# PageTurner.net
KiCad netlist of a schematic drawn in EAGLE
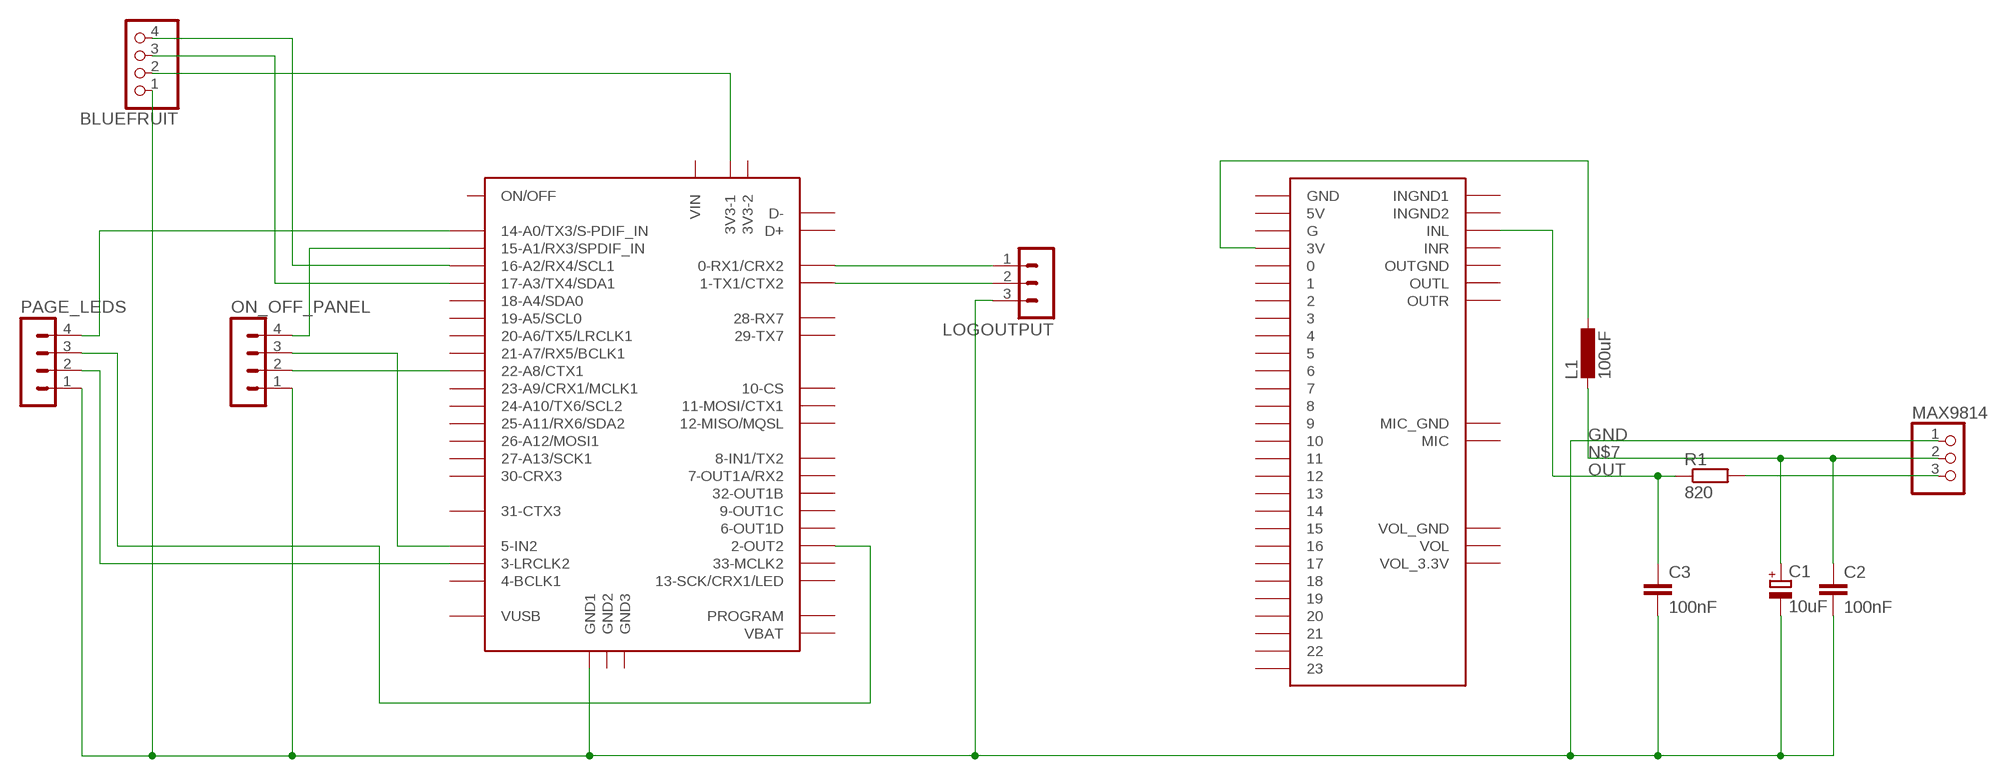
[diagram p0: schematic, sheet 1]

(export (version "E")
  (design (tool "Eeschema 10.0.6"))
  (components
    (comp (ref "BLUEFRUIT")
      (value "PINHD-1X4")
      (footprint "eagle-import:1X04")
      (libsource (lib "eagle-import") (part "PINHD-1X4"))
    )
    (comp (ref "C1")
      (value "10uF")
      (footprint "eagle-import:E2-4")
      (libsource (lib "eagle-import") (part "CPOL-EUE2-4"))
    )
    (comp (ref "C2")
      (value "100nF")
      (footprint "eagle-import:C025-040X050")
      (libsource (lib "eagle-import") (part "C-EU025-040X050"))
    )
    (comp (ref "C3")
      (value "100nF")
      (footprint "eagle-import:C025-040X050")
      (libsource (lib "eagle-import") (part "C-EU025-040X050"))
    )
    (comp (ref "L1")
      (value "100uF")
      (footprint "eagle-import:0207_5V")
      (libsource (lib "eagle-import") (part "L-EU0207/5V"))
    )
    (comp (ref "LOGOUTPUT")
      (value "MA03-1")
      (footprint "eagle-import:MA03-1")
      (libsource (lib "eagle-import") (part "MA03-1"))
    )
    (comp (ref "MAX9814")
      (value "PINHD-1X3")
      (footprint "eagle-import:1X03")
      (libsource (lib "eagle-import") (part "PINHD-1X3"))
    )
    (comp (ref "ON_OFF_PANEL")
      (value "MA04-1")
      (footprint "eagle-import:MA04-1")
      (libsource (lib "eagle-import") (part "MA04-1"))
    )
    (comp (ref "PAGE_LEDS")
      (value "MA04-1")
      (footprint "eagle-import:MA04-1")
      (libsource (lib "eagle-import") (part "MA04-1"))
    )
    (comp (ref "R1")
      (value "820")
      (footprint "eagle-import:0207_7")
      (libsource (lib "eagle-import") (part "R-EU_0207/7"))
    )
    (comp (ref "U$1")
      (value "TEENSY40")
      (footprint "eagle-import:TEENSY40")
      (libsource (lib "eagle-import") (part "TEENSY40"))
    )
    (comp (ref "U$2")
      (value "AUDIOSHIELD")
      (footprint "eagle-import:AUDIOSHIELD")
      (libsource (lib "eagle-import") (part "AUDIOSHIELD"))
    )
  )
  (nets
    (net (code "1") (name "/GND") (class "Default")
      (node (ref "BLUEFRUIT") (pin "1") (pinfunction "1_1") (pintype "passive"))
      (node (ref "C1") (pin "-") (pinfunction "-_-") (pintype "passive"))
      (node (ref "C2") (pin "2") (pinfunction "2_2") (pintype "passive"))
      (node (ref "C3") (pin "2") (pinfunction "2_2") (pintype "passive"))
      (node (ref "LOGOUTPUT") (pin "3") (pinfunction "3_3") (pintype "passive"))
      (node (ref "MAX9814") (pin "1") (pinfunction "1_1") (pintype "passive"))
      (node (ref "ON_OFF_PANEL") (pin "1") (pinfunction "1_1") (pintype "passive"))
      (node (ref "PAGE_LEDS") (pin "1") (pinfunction "1_1") (pintype "passive"))
      (node (ref "U$1") (pin "GND1") (pinfunction "GND1_GND1") (pintype "bidirectional"))
    )
    (net (code "2") (name "/N$7") (class "Default")
      (node (ref "C1") (pin "+") (pinfunction "+_+") (pintype "passive"))
      (node (ref "C2") (pin "1") (pinfunction "1_1") (pintype "passive"))
      (node (ref "L1") (pin "2") (pinfunction "2_2") (pintype "passive"))
      (node (ref "MAX9814") (pin "2") (pinfunction "2_2") (pintype "passive"))
    )
    (net (code "3") (name "/OUT") (class "Default")
      (node (ref "C3") (pin "1") (pinfunction "1_1") (pintype "passive"))
      (node (ref "R1") (pin "1") (pinfunction "1_1") (pintype "passive"))
      (node (ref "U$2") (pin "INL") (pinfunction "INL_INL") (pintype "input"))
    )
    (net (code "4") (name "Net-(BLUEFRUIT-Pad2)") (class "Default")
      (node (ref "BLUEFRUIT") (pin "2") (pinfunction "2_2") (pintype "passive"))
      (node (ref "U$1") (pin "3V3-1") (pinfunction "3V3-1_3V3-1") (pintype "bidirectional"))
    )
    (net (code "5") (name "Net-(BLUEFRUIT-Pad3)") (class "Default")
      (node (ref "BLUEFRUIT") (pin "3") (pinfunction "3_3") (pintype "passive"))
      (node (ref "U$1") (pin "17-A3/TX4/SDA1") (pinfunction "17-A3/TX4/SDA1_17-A3/TX4/SDA1") (pintype "bidirectional"))
    )
    (net (code "6") (name "Net-(BLUEFRUIT-Pad4)") (class "Default")
      (node (ref "BLUEFRUIT") (pin "4") (pinfunction "4_4") (pintype "passive"))
      (node (ref "U$1") (pin "16-A2/RX4/SCL1") (pinfunction "16-A2/RX4/SCL1_16-A2/RX4/SCL1") (pintype "bidirectional"))
    )
    (net (code "7") (name "Net-(L1-Pad1)") (class "Default")
      (node (ref "L1") (pin "1") (pinfunction "1_1") (pintype "passive"))
      (node (ref "U$2") (pin "3V") (pinfunction "3V_3V") (pintype "bidirectional"))
    )
    (net (code "8") (name "Net-(MAX9814-Pad3)") (class "Default")
      (node (ref "MAX9814") (pin "3") (pinfunction "3_3") (pintype "passive"))
      (node (ref "R1") (pin "2") (pinfunction "2_2") (pintype "passive"))
    )
    (net (code "9") (name "Net-(ON_OFF_PANEL-Pad2)") (class "Default")
      (node (ref "ON_OFF_PANEL") (pin "2") (pinfunction "2_2") (pintype "passive"))
      (node (ref "U$1") (pin "22-A8/CTX1") (pinfunction "22-A8/CTX1_22-A8/CTX1") (pintype "bidirectional"))
    )
    (net (code "10") (name "Net-(ON_OFF_PANEL-Pad3)") (class "Default")
      (node (ref "ON_OFF_PANEL") (pin "3") (pinfunction "3_3") (pintype "passive"))
      (node (ref "U$1") (pin "5-IN2") (pinfunction "5-IN2_5-IN2") (pintype "bidirectional"))
    )
    (net (code "11") (name "Net-(PAGE_LEDS-Pad2)") (class "Default")
      (node (ref "PAGE_LEDS") (pin "2") (pinfunction "2_2") (pintype "passive"))
      (node (ref "U$1") (pin "3-LRCLK2") (pinfunction "3-LRCLK2_3-LRCLK2") (pintype "bidirectional"))
    )
    (net (code "12") (name "Net-(PAGE_LEDS-Pad3)") (class "Default")
      (node (ref "PAGE_LEDS") (pin "3") (pinfunction "3_3") (pintype "passive"))
      (node (ref "U$1") (pin "2-OUT2") (pinfunction "2-OUT2_2-OUT2") (pintype "bidirectional"))
    )
    (net (code "13") (name "Net-(U$1-0-RX1{slash}CRX2)") (class "Default")
      (node (ref "LOGOUTPUT") (pin "1") (pinfunction "1_1") (pintype "passive"))
      (node (ref "U$1") (pin "0-RX1") (pinfunction "0-RX1/CRX2_0-RX1") (pintype "bidirectional"))
    )
    (net (code "14") (name "Net-(U$1-1-TX1{slash}CTX2)") (class "Default")
      (node (ref "LOGOUTPUT") (pin "2") (pinfunction "2_2") (pintype "passive"))
      (node (ref "U$1") (pin "1-TX1") (pinfunction "1-TX1/CTX2_1-TX1") (pintype "bidirectional"))
    )
    (net (code "15") (name "Net-(U$1-14-A0{slash}TX3{slash}S-PDIF_IN)") (class "Default")
      (node (ref "PAGE_LEDS") (pin "4") (pinfunction "4_4") (pintype "passive"))
      (node (ref "U$1") (pin "14-A0/TX3/S-PFI_OUT") (pinfunction "14-A0/TX3/S-PDIF_IN_14-A0/TX3/S-PFI_OUT") (pintype "bidirectional"))
    )
    (net (code "16") (name "Net-(U$1-15-A1{slash}RX3{slash}SPDIF_IN)") (class "Default")
      (node (ref "ON_OFF_PANEL") (pin "4") (pinfunction "4_4") (pintype "passive"))
      (node (ref "U$1") (pin "15-A1/RX3/S-PDIF_IN") (pinfunction "15-A1/RX3/SPDIF_IN_15-A1/RX3/S-PDIF_IN") (pintype "bidirectional"))
    )
    (net (code "17") (name "unconnected-(U$1-4-BCLK1-Pad4-BCLK2)") (class "Default")
      (node (ref "U$1") (pin "4-BCLK2") (pinfunction "4-BCLK1_4-BCLK2") (pintype "bidirectional"))
    )
    (net (code "18") (name "unconnected-(U$1-7-OUT1A{slash}RX2-Pad7-RX2{slash}OUT1A)") (class "Default")
      (node (ref "U$1") (pin "7-RX2/OUT1A") (pinfunction "7-OUT1A/RX2_7-RX2/OUT1A") (pintype "bidirectional"))
    )
    (net (code "19") (name "unconnected-(U$1-8-IN1{slash}TX2-Pad8-TX2{slash}IN1)") (class "Default")
      (node (ref "U$1") (pin "8-TX2/IN1") (pinfunction "8-IN1/TX2_8-TX2/IN1") (pintype "bidirectional"))
    )
    (net (code "20") (name "unconnected-(U$1-10-CS-Pad10-CS{slash}MQSR)") (class "Default")
      (node (ref "U$1") (pin "10-CS/MQSR") (pinfunction "10-CS_10-CS/MQSR") (pintype "bidirectional"))
    )
    (net (code "21") (name "unconnected-(U$1-12-MISO{slash}MQSL-Pad12-MIO{slash}MQSL)") (class "Default")
      (node (ref "U$1") (pin "12-MIO/MQSL") (pinfunction "12-MISO/MQSL_12-MIO/MQSL") (pintype "bidirectional"))
    )
    (net (code "22") (name "unconnected-(U$1-23-A9{slash}CRX1{slash}MCLK1-Pad23-A9{slash}CRX1{slash}CCLK1)") (class "Default")
      (node (ref "U$1") (pin "23-A9/CRX1/CCLK1") (pinfunction "23-A9/CRX1/MCLK1_23-A9/CRX1/CCLK1") (pintype "bidirectional"))
    )
    (net (code "23") (name "unconnected-(U$1-25-A11{slash}RX6{slash}SDA2-Pad25-A11{slash}SDA2)") (class "Default")
      (node (ref "U$1") (pin "25-A11/SDA2") (pinfunction "25-A11/RX6/SDA2_25-A11/SDA2") (pintype "bidirectional"))
    )
    (net (code "24") (name "unconnected-(U$1-32-OUT1B-Pad32-OUTB1)") (class "Default")
      (node (ref "U$1") (pin "32-OUTB1") (pinfunction "32-OUT1B_32-OUTB1") (pintype "bidirectional"))
    )
    (net (code "25") (name "unconnected-(U$1-Pad3V3-2)") (class "Default")
      (node (ref "U$1") (pin "3V3-2") (pinfunction "3V3-2_3V3-2") (pintype "bidirectional"))
    )
    (net (code "26") (name "unconnected-(U$1-Pad6-OUT1D)") (class "Default")
      (node (ref "U$1") (pin "6-OUT1D") (pinfunction "6-OUT1D_6-OUT1D") (pintype "bidirectional"))
    )
    (net (code "27") (name "unconnected-(U$1-Pad9-OUT1C)") (class "Default")
      (node (ref "U$1") (pin "9-OUT1C") (pinfunction "9-OUT1C_9-OUT1C") (pintype "bidirectional"))
    )
    (net (code "28") (name "unconnected-(U$1-Pad11-MOSI{slash}CTX1)") (class "Default")
      (node (ref "U$1") (pin "11-MOSI/CTX1") (pinfunction "11-MOSI/CTX1_11-MOSI/CTX1") (pintype "bidirectional"))
    )
    (net (code "29") (name "unconnected-(U$1-Pad13-SCK{slash}CRX1{slash}LED)") (class "Default")
      (node (ref "U$1") (pin "13-SCK/CRX1/LED") (pinfunction "13-SCK/CRX1/LED_13-SCK/CRX1/LED") (pintype "bidirectional"))
    )
    (net (code "30") (name "unconnected-(U$1-Pad18-A4{slash}SDA0)") (class "Default")
      (node (ref "U$1") (pin "18-A4/SDA0") (pinfunction "18-A4/SDA0_18-A4/SDA0") (pintype "bidirectional"))
    )
    (net (code "31") (name "unconnected-(U$1-Pad19-A5{slash}SCL0)") (class "Default")
      (node (ref "U$1") (pin "19-A5/SCL0") (pinfunction "19-A5/SCL0_19-A5/SCL0") (pintype "bidirectional"))
    )
    (net (code "32") (name "unconnected-(U$1-Pad20-A6{slash}TX5{slash}LRCLK1)") (class "Default")
      (node (ref "U$1") (pin "20-A6/TX5/LRCLK1") (pinfunction "20-A6/TX5/LRCLK1_20-A6/TX5/LRCLK1") (pintype "bidirectional"))
    )
    (net (code "33") (name "unconnected-(U$1-Pad21-A7{slash}RX5{slash}BCLK1)") (class "Default")
      (node (ref "U$1") (pin "21-A7/RX5/BCLK1") (pinfunction "21-A7/RX5/BCLK1_21-A7/RX5/BCLK1") (pintype "bidirectional"))
    )
    (net (code "34") (name "unconnected-(U$1-Pad24-A10{slash}TX6{slash}SCL2)") (class "Default")
      (node (ref "U$1") (pin "24-A10/TX6/SCL2") (pinfunction "24-A10/TX6/SCL2_24-A10/TX6/SCL2") (pintype "bidirectional"))
    )
    (net (code "35") (name "unconnected-(U$1-Pad26-A12{slash}MOSI1)") (class "Default")
      (node (ref "U$1") (pin "26-A12/MOSI1") (pinfunction "26-A12/MOSI1_26-A12/MOSI1") (pintype "bidirectional"))
    )
    (net (code "36") (name "unconnected-(U$1-Pad27-A13{slash}SCK1)") (class "Default")
      (node (ref "U$1") (pin "27-A13/SCK1") (pinfunction "27-A13/SCK1_27-A13/SCK1") (pintype "bidirectional"))
    )
    (net (code "37") (name "unconnected-(U$1-Pad28-RX7)") (class "Default")
      (node (ref "U$1") (pin "28-RX7") (pinfunction "28-RX7_28-RX7") (pintype "bidirectional"))
    )
    (net (code "38") (name "unconnected-(U$1-Pad29-TX7)") (class "Default")
      (node (ref "U$1") (pin "29-TX7") (pinfunction "29-TX7_29-TX7") (pintype "bidirectional"))
    )
    (net (code "39") (name "unconnected-(U$1-Pad30-CRX3)") (class "Default")
      (node (ref "U$1") (pin "30-CRX3") (pinfunction "30-CRX3_30-CRX3") (pintype "bidirectional"))
    )
    (net (code "40") (name "unconnected-(U$1-Pad31-CTX3)") (class "Default")
      (node (ref "U$1") (pin "31-CTX3") (pinfunction "31-CTX3_31-CTX3") (pintype "bidirectional"))
    )
    (net (code "41") (name "unconnected-(U$1-Pad33-MCLK2)") (class "Default")
      (node (ref "U$1") (pin "33-MCLK2") (pinfunction "33-MCLK2_33-MCLK2") (pintype "bidirectional"))
    )
    (net (code "42") (name "unconnected-(U$1-PadD+)") (class "Default")
      (node (ref "U$1") (pin "D+") (pinfunction "D+_D+") (pintype "bidirectional"))
    )
    (net (code "43") (name "unconnected-(U$1-PadD-)") (class "Default")
      (node (ref "U$1") (pin "D-") (pinfunction "D-_D-") (pintype "bidirectional"))
    )
    (net (code "44") (name "unconnected-(U$1-PadGND2)") (class "Default")
      (node (ref "U$1") (pin "GND2") (pinfunction "GND2_GND2") (pintype "bidirectional"))
    )
    (net (code "45") (name "unconnected-(U$1-PadGND3)") (class "Default")
      (node (ref "U$1") (pin "GND3") (pinfunction "GND3_GND3") (pintype "bidirectional"))
    )
    (net (code "46") (name "unconnected-(U$1-PadON{slash}OFF)") (class "Default")
      (node (ref "U$1") (pin "ON/OFF") (pinfunction "ON/OFF_ON/OFF") (pintype "bidirectional"))
    )
    (net (code "47") (name "unconnected-(U$1-PadPROGRAM)") (class "Default")
      (node (ref "U$1") (pin "PROGRAM") (pinfunction "PROGRAM_PROGRAM") (pintype "bidirectional"))
    )
    (net (code "48") (name "unconnected-(U$1-PadVBAT)") (class "Default")
      (node (ref "U$1") (pin "VBAT") (pinfunction "VBAT_VBAT") (pintype "bidirectional"))
    )
    (net (code "49") (name "unconnected-(U$1-PadVIN)") (class "Default")
      (node (ref "U$1") (pin "VIN") (pinfunction "VIN_VIN") (pintype "bidirectional"))
    )
    (net (code "50") (name "unconnected-(U$1-PadVUSB)") (class "Default")
      (node (ref "U$1") (pin "VUSB") (pinfunction "VUSB_VUSB") (pintype "bidirectional"))
    )
    (net (code "51") (name "unconnected-(U$2-MIC_GND-PadGND_MIC)") (class "Default")
      (node (ref "U$2") (pin "GND_MIC") (pinfunction "MIC_GND_GND_MIC") (pintype "bidirectional"))
    )
    (net (code "52") (name "unconnected-(U$2-Pad0)") (class "Default")
      (node (ref "U$2") (pin "0") (pinfunction "0_0") (pintype "bidirectional"))
    )
    (net (code "53") (name "unconnected-(U$2-Pad1)") (class "Default")
      (node (ref "U$2") (pin "1") (pinfunction "1_1") (pintype "bidirectional"))
    )
    (net (code "54") (name "unconnected-(U$2-Pad2)") (class "Default")
      (node (ref "U$2") (pin "2") (pinfunction "2_2") (pintype "bidirectional"))
    )
    (net (code "55") (name "unconnected-(U$2-Pad3)") (class "Default")
      (node (ref "U$2") (pin "3") (pinfunction "3_3") (pintype "bidirectional"))
    )
    (net (code "56") (name "unconnected-(U$2-Pad4)") (class "Default")
      (node (ref "U$2") (pin "4") (pinfunction "4_4") (pintype "bidirectional"))
    )
    (net (code "57") (name "unconnected-(U$2-Pad5)") (class "Default")
      (node (ref "U$2") (pin "5") (pinfunction "5_5") (pintype "bidirectional"))
    )
    (net (code "58") (name "unconnected-(U$2-Pad5V)") (class "Default")
      (node (ref "U$2") (pin "5V") (pinfunction "5V_5V") (pintype "bidirectional"))
    )
    (net (code "59") (name "unconnected-(U$2-Pad6)") (class "Default")
      (node (ref "U$2") (pin "6") (pinfunction "6_6") (pintype "bidirectional"))
    )
    (net (code "60") (name "unconnected-(U$2-Pad7)") (class "Default")
      (node (ref "U$2") (pin "7") (pinfunction "7_7") (pintype "bidirectional"))
    )
    (net (code "61") (name "unconnected-(U$2-Pad8)") (class "Default")
      (node (ref "U$2") (pin "8") (pinfunction "8_8") (pintype "bidirectional"))
    )
    (net (code "62") (name "unconnected-(U$2-Pad9)") (class "Default")
      (node (ref "U$2") (pin "9") (pinfunction "9_9") (pintype "bidirectional"))
    )
    (net (code "63") (name "unconnected-(U$2-Pad10)") (class "Default")
      (node (ref "U$2") (pin "10") (pinfunction "10_10") (pintype "bidirectional"))
    )
    (net (code "64") (name "unconnected-(U$2-Pad11)") (class "Default")
      (node (ref "U$2") (pin "11") (pinfunction "11_11") (pintype "bidirectional"))
    )
    (net (code "65") (name "unconnected-(U$2-Pad12)") (class "Default")
      (node (ref "U$2") (pin "12") (pinfunction "12_12") (pintype "bidirectional"))
    )
    (net (code "66") (name "unconnected-(U$2-Pad13)") (class "Default")
      (node (ref "U$2") (pin "13") (pinfunction "13_13") (pintype "bidirectional"))
    )
    (net (code "67") (name "unconnected-(U$2-Pad14)") (class "Default")
      (node (ref "U$2") (pin "14") (pinfunction "14_14") (pintype "bidirectional"))
    )
    (net (code "68") (name "unconnected-(U$2-Pad15)") (class "Default")
      (node (ref "U$2") (pin "15") (pinfunction "15_15") (pintype "bidirectional"))
    )
    (net (code "69") (name "unconnected-(U$2-Pad16)") (class "Default")
      (node (ref "U$2") (pin "16") (pinfunction "16_16") (pintype "bidirectional"))
    )
    (net (code "70") (name "unconnected-(U$2-Pad17)") (class "Default")
      (node (ref "U$2") (pin "17") (pinfunction "17_17") (pintype "bidirectional"))
    )
    (net (code "71") (name "unconnected-(U$2-Pad18)") (class "Default")
      (node (ref "U$2") (pin "18") (pinfunction "18_18") (pintype "bidirectional"))
    )
    (net (code "72") (name "unconnected-(U$2-Pad19)") (class "Default")
      (node (ref "U$2") (pin "19") (pinfunction "19_19") (pintype "bidirectional"))
    )
    (net (code "73") (name "unconnected-(U$2-Pad20)") (class "Default")
      (node (ref "U$2") (pin "20") (pinfunction "20_20") (pintype "bidirectional"))
    )
    (net (code "74") (name "unconnected-(U$2-Pad21)") (class "Default")
      (node (ref "U$2") (pin "21") (pinfunction "21_21") (pintype "bidirectional"))
    )
    (net (code "75") (name "unconnected-(U$2-Pad22)") (class "Default")
      (node (ref "U$2") (pin "22") (pinfunction "22_22") (pintype "bidirectional"))
    )
    (net (code "76") (name "unconnected-(U$2-Pad23)") (class "Default")
      (node (ref "U$2") (pin "23") (pinfunction "23_23") (pintype "bidirectional"))
    )
    (net (code "77") (name "unconnected-(U$2-PadG)") (class "Default")
      (node (ref "U$2") (pin "G") (pinfunction "G_G") (pintype "bidirectional"))
    )
    (net (code "78") (name "unconnected-(U$2-PadGND)") (class "Default")
      (node (ref "U$2") (pin "GND") (pinfunction "GND_GND") (pintype "bidirectional"))
    )
    (net (code "79") (name "unconnected-(U$2-PadINGND1)") (class "Default")
      (node (ref "U$2") (pin "INGND1") (pinfunction "INGND1_INGND1") (pintype "bidirectional"))
    )
    (net (code "80") (name "unconnected-(U$2-PadINGND2)") (class "Default")
      (node (ref "U$2") (pin "INGND2") (pinfunction "INGND2_INGND2") (pintype "bidirectional"))
    )
    (net (code "81") (name "unconnected-(U$2-PadINR)") (class "Default")
      (node (ref "U$2") (pin "INR") (pinfunction "INR_INR") (pintype "input"))
    )
    (net (code "82") (name "unconnected-(U$2-PadMIC)") (class "Default")
      (node (ref "U$2") (pin "MIC") (pinfunction "MIC_MIC") (pintype "input"))
    )
    (net (code "83") (name "unconnected-(U$2-PadOUTGND)") (class "Default")
      (node (ref "U$2") (pin "OUTGND") (pinfunction "OUTGND_OUTGND") (pintype "bidirectional"))
    )
    (net (code "84") (name "unconnected-(U$2-PadOUTL)") (class "Default")
      (node (ref "U$2") (pin "OUTL") (pinfunction "OUTL_OUTL") (pintype "output"))
    )
    (net (code "85") (name "unconnected-(U$2-PadOUTR)") (class "Default")
      (node (ref "U$2") (pin "OUTR") (pinfunction "OUTR_OUTR") (pintype "output"))
    )
    (net (code "86") (name "unconnected-(U$2-PadVOL)") (class "Default")
      (node (ref "U$2") (pin "VOL") (pinfunction "VOL_VOL") (pintype "input"))
    )
    (net (code "87") (name "unconnected-(U$2-PadVOL_3.3V)") (class "Default")
      (node (ref "U$2") (pin "VOL_3.3V") (pinfunction "VOL_3.3V_VOL_3.3V") (pintype "bidirectional"))
    )
    (net (code "88") (name "unconnected-(U$2-PadVOL_GND)") (class "Default")
      (node (ref "U$2") (pin "VOL_GND") (pinfunction "VOL_GND_VOL_GND") (pintype "bidirectional"))
    )
  )
)
